# pwr_part.net
KiCad netlist of a schematic drawn in EAGLE
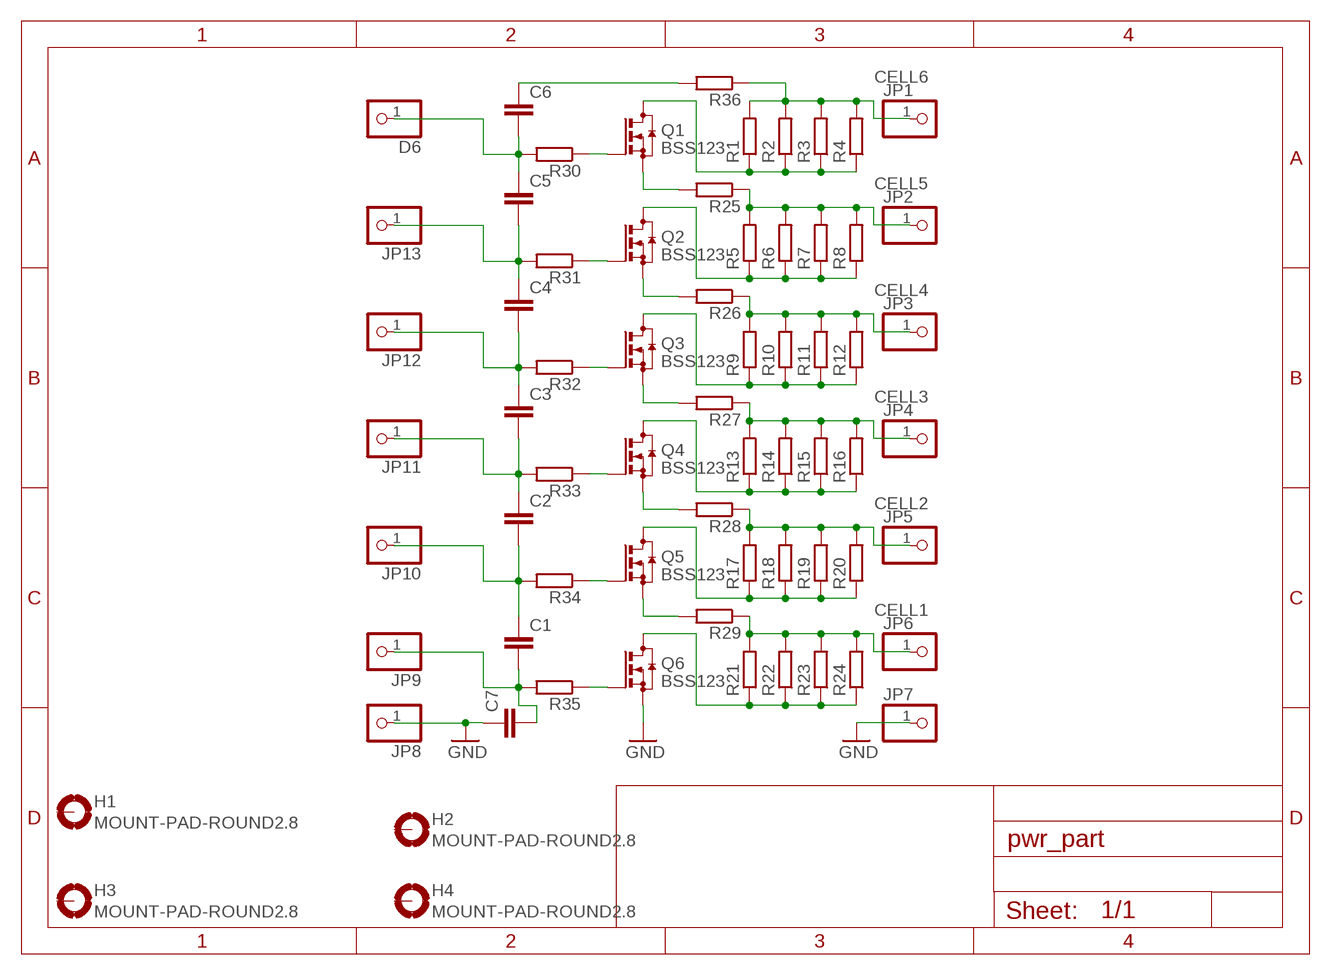
[diagram p0: schematic, sheet 1]

(export (version "E")
  (design (tool "Eeschema 10.0.6"))
  (components
    (comp (ref "C1")
      (value "C-EUC0805K")
      (footprint "eagle-import:C0805K")
      (libsource (lib "eagle-import") (part "C-EUC0805K"))
    )
    (comp (ref "C2")
      (value "C-EUC0805K")
      (footprint "eagle-import:C0805K")
      (libsource (lib "eagle-import") (part "C-EUC0805K"))
    )
    (comp (ref "C3")
      (value "C-EUC0805K")
      (footprint "eagle-import:C0805K")
      (libsource (lib "eagle-import") (part "C-EUC0805K"))
    )
    (comp (ref "C4")
      (value "C-EUC0805K")
      (footprint "eagle-import:C0805K")
      (libsource (lib "eagle-import") (part "C-EUC0805K"))
    )
    (comp (ref "C5")
      (value "C-EUC0805K")
      (footprint "eagle-import:C0805K")
      (libsource (lib "eagle-import") (part "C-EUC0805K"))
    )
    (comp (ref "C6")
      (value "C-EUC0805K")
      (footprint "eagle-import:C0805K")
      (libsource (lib "eagle-import") (part "C-EUC0805K"))
    )
    (comp (ref "C7")
      (value "C-EUC0805K")
      (footprint "eagle-import:C0805K")
      (libsource (lib "eagle-import") (part "C-EUC0805K"))
    )
    (comp (ref "D6")
      (value "PINHD-1X1")
      (footprint "eagle-import:1X01")
      (libsource (lib "eagle-import") (part "PINHD-1X1"))
    )
    (comp (ref "H1")
      (value "MOUNT-PAD-ROUND2.8")
      (footprint "eagle-import:2,8-PAD")
      (libsource (lib "eagle-import") (part "MOUNT-PAD-ROUND2.8"))
    )
    (comp (ref "H2")
      (value "MOUNT-PAD-ROUND2.8")
      (footprint "eagle-import:2,8-PAD")
      (libsource (lib "eagle-import") (part "MOUNT-PAD-ROUND2.8"))
    )
    (comp (ref "H3")
      (value "MOUNT-PAD-ROUND2.8")
      (footprint "eagle-import:2,8-PAD")
      (libsource (lib "eagle-import") (part "MOUNT-PAD-ROUND2.8"))
    )
    (comp (ref "H4")
      (value "MOUNT-PAD-ROUND2.8")
      (footprint "eagle-import:2,8-PAD")
      (libsource (lib "eagle-import") (part "MOUNT-PAD-ROUND2.8"))
    )
    (comp (ref "JP1")
      (value "PINHD-1X1")
      (footprint "eagle-import:1X01")
      (libsource (lib "eagle-import") (part "PINHD-1X1"))
    )
    (comp (ref "JP2")
      (value "PINHD-1X1")
      (footprint "eagle-import:1X01")
      (libsource (lib "eagle-import") (part "PINHD-1X1"))
    )
    (comp (ref "JP3")
      (value "PINHD-1X1")
      (footprint "eagle-import:1X01")
      (libsource (lib "eagle-import") (part "PINHD-1X1"))
    )
    (comp (ref "JP4")
      (value "PINHD-1X1")
      (footprint "eagle-import:1X01")
      (libsource (lib "eagle-import") (part "PINHD-1X1"))
    )
    (comp (ref "JP5")
      (value "PINHD-1X1")
      (footprint "eagle-import:1X01")
      (libsource (lib "eagle-import") (part "PINHD-1X1"))
    )
    (comp (ref "JP6")
      (value "PINHD-1X1")
      (footprint "eagle-import:1X01")
      (libsource (lib "eagle-import") (part "PINHD-1X1"))
    )
    (comp (ref "JP7")
      (value "PINHD-1X1")
      (footprint "eagle-import:1X01")
      (libsource (lib "eagle-import") (part "PINHD-1X1"))
    )
    (comp (ref "JP8")
      (value "PINHD-1X1")
      (footprint "eagle-import:1X01")
      (libsource (lib "eagle-import") (part "PINHD-1X1"))
    )
    (comp (ref "JP9")
      (value "PINHD-1X1")
      (footprint "eagle-import:1X01")
      (libsource (lib "eagle-import") (part "PINHD-1X1"))
    )
    (comp (ref "JP10")
      (value "PINHD-1X1")
      (footprint "eagle-import:1X01")
      (libsource (lib "eagle-import") (part "PINHD-1X1"))
    )
    (comp (ref "JP11")
      (value "PINHD-1X1")
      (footprint "eagle-import:1X01")
      (libsource (lib "eagle-import") (part "PINHD-1X1"))
    )
    (comp (ref "JP12")
      (value "PINHD-1X1")
      (footprint "eagle-import:1X01")
      (libsource (lib "eagle-import") (part "PINHD-1X1"))
    )
    (comp (ref "JP13")
      (value "PINHD-1X1")
      (footprint "eagle-import:1X01")
      (libsource (lib "eagle-import") (part "PINHD-1X1"))
    )
    (comp (ref "Q1")
      (value "BSS123")
      (footprint "eagle-import:SOT23")
      (libsource (lib "eagle-import") (part "BSS123"))
    )
    (comp (ref "Q2")
      (value "BSS123")
      (footprint "eagle-import:SOT23")
      (libsource (lib "eagle-import") (part "BSS123"))
    )
    (comp (ref "Q3")
      (value "BSS123")
      (footprint "eagle-import:SOT23")
      (libsource (lib "eagle-import") (part "BSS123"))
    )
    (comp (ref "Q4")
      (value "BSS123")
      (footprint "eagle-import:SOT23")
      (libsource (lib "eagle-import") (part "BSS123"))
    )
    (comp (ref "Q5")
      (value "BSS123")
      (footprint "eagle-import:SOT23")
      (libsource (lib "eagle-import") (part "BSS123"))
    )
    (comp (ref "Q6")
      (value "BSS123")
      (footprint "eagle-import:SOT23")
      (libsource (lib "eagle-import") (part "BSS123"))
    )
    (comp (ref "R1")
      (value "R-EU_R1206")
      (footprint "eagle-import:R1206")
      (libsource (lib "eagle-import") (part "R-EU_R1206"))
    )
    (comp (ref "R2")
      (value "R-EU_R1206")
      (footprint "eagle-import:R1206")
      (libsource (lib "eagle-import") (part "R-EU_R1206"))
    )
    (comp (ref "R3")
      (value "R-EU_R1206")
      (footprint "eagle-import:R1206")
      (libsource (lib "eagle-import") (part "R-EU_R1206"))
    )
    (comp (ref "R4")
      (value "R-EU_R1206")
      (footprint "eagle-import:R1206")
      (libsource (lib "eagle-import") (part "R-EU_R1206"))
    )
    (comp (ref "R5")
      (value "R-EU_R1206")
      (footprint "eagle-import:R1206")
      (libsource (lib "eagle-import") (part "R-EU_R1206"))
    )
    (comp (ref "R6")
      (value "R-EU_R1206")
      (footprint "eagle-import:R1206")
      (libsource (lib "eagle-import") (part "R-EU_R1206"))
    )
    (comp (ref "R7")
      (value "R-EU_R1206")
      (footprint "eagle-import:R1206")
      (libsource (lib "eagle-import") (part "R-EU_R1206"))
    )
    (comp (ref "R8")
      (value "R-EU_R1206")
      (footprint "eagle-import:R1206")
      (libsource (lib "eagle-import") (part "R-EU_R1206"))
    )
    (comp (ref "R9")
      (value "R-EU_R1206")
      (footprint "eagle-import:R1206")
      (libsource (lib "eagle-import") (part "R-EU_R1206"))
    )
    (comp (ref "R10")
      (value "R-EU_R1206")
      (footprint "eagle-import:R1206")
      (libsource (lib "eagle-import") (part "R-EU_R1206"))
    )
    (comp (ref "R11")
      (value "R-EU_R1206")
      (footprint "eagle-import:R1206")
      (libsource (lib "eagle-import") (part "R-EU_R1206"))
    )
    (comp (ref "R12")
      (value "R-EU_R1206")
      (footprint "eagle-import:R1206")
      (libsource (lib "eagle-import") (part "R-EU_R1206"))
    )
    (comp (ref "R13")
      (value "R-EU_R1206")
      (footprint "eagle-import:R1206")
      (libsource (lib "eagle-import") (part "R-EU_R1206"))
    )
    (comp (ref "R14")
      (value "R-EU_R1206")
      (footprint "eagle-import:R1206")
      (libsource (lib "eagle-import") (part "R-EU_R1206"))
    )
    (comp (ref "R15")
      (value "R-EU_R1206")
      (footprint "eagle-import:R1206")
      (libsource (lib "eagle-import") (part "R-EU_R1206"))
    )
    (comp (ref "R16")
      (value "R-EU_R1206")
      (footprint "eagle-import:R1206")
      (libsource (lib "eagle-import") (part "R-EU_R1206"))
    )
    (comp (ref "R17")
      (value "R-EU_R1206")
      (footprint "eagle-import:R1206")
      (libsource (lib "eagle-import") (part "R-EU_R1206"))
    )
    (comp (ref "R18")
      (value "R-EU_R1206")
      (footprint "eagle-import:R1206")
      (libsource (lib "eagle-import") (part "R-EU_R1206"))
    )
    (comp (ref "R19")
      (value "R-EU_R1206")
      (footprint "eagle-import:R1206")
      (libsource (lib "eagle-import") (part "R-EU_R1206"))
    )
    (comp (ref "R20")
      (value "R-EU_R1206")
      (footprint "eagle-import:R1206")
      (libsource (lib "eagle-import") (part "R-EU_R1206"))
    )
    (comp (ref "R21")
      (value "R-EU_R1206")
      (footprint "eagle-import:R1206")
      (libsource (lib "eagle-import") (part "R-EU_R1206"))
    )
    (comp (ref "R22")
      (value "R-EU_R1206")
      (footprint "eagle-import:R1206")
      (libsource (lib "eagle-import") (part "R-EU_R1206"))
    )
    (comp (ref "R23")
      (value "R-EU_R1206")
      (footprint "eagle-import:R1206")
      (libsource (lib "eagle-import") (part "R-EU_R1206"))
    )
    (comp (ref "R24")
      (value "R-EU_R1206")
      (footprint "eagle-import:R1206")
      (libsource (lib "eagle-import") (part "R-EU_R1206"))
    )
    (comp (ref "R25")
      (value "R-EU_0411/3V")
      (footprint "eagle-import:0411V")
      (libsource (lib "eagle-import") (part "R-EU_0411/3V"))
    )
    (comp (ref "R26")
      (value "R-EU_0411/3V")
      (footprint "eagle-import:0411V")
      (libsource (lib "eagle-import") (part "R-EU_0411/3V"))
    )
    (comp (ref "R27")
      (value "R-EU_0411/3V")
      (footprint "eagle-import:0411V")
      (libsource (lib "eagle-import") (part "R-EU_0411/3V"))
    )
    (comp (ref "R28")
      (value "R-EU_0411/3V")
      (footprint "eagle-import:0411V")
      (libsource (lib "eagle-import") (part "R-EU_0411/3V"))
    )
    (comp (ref "R29")
      (value "R-EU_0411/3V")
      (footprint "eagle-import:0411V")
      (libsource (lib "eagle-import") (part "R-EU_0411/3V"))
    )
    (comp (ref "R30")
      (value "R-EU_R1206")
      (footprint "eagle-import:R1206")
      (libsource (lib "eagle-import") (part "R-EU_R1206"))
    )
    (comp (ref "R31")
      (value "R-EU_R1206")
      (footprint "eagle-import:R1206")
      (libsource (lib "eagle-import") (part "R-EU_R1206"))
    )
    (comp (ref "R32")
      (value "R-EU_R1206")
      (footprint "eagle-import:R1206")
      (libsource (lib "eagle-import") (part "R-EU_R1206"))
    )
    (comp (ref "R33")
      (value "R-EU_R1206")
      (footprint "eagle-import:R1206")
      (libsource (lib "eagle-import") (part "R-EU_R1206"))
    )
    (comp (ref "R34")
      (value "R-EU_R1206")
      (footprint "eagle-import:R1206")
      (libsource (lib "eagle-import") (part "R-EU_R1206"))
    )
    (comp (ref "R35")
      (value "R-EU_R1206")
      (footprint "eagle-import:R1206")
      (libsource (lib "eagle-import") (part "R-EU_R1206"))
    )
    (comp (ref "R36")
      (value "R-EU_0411/3V")
      (footprint "eagle-import:0411V")
      (libsource (lib "eagle-import") (part "R-EU_0411/3V"))
    )
  )
  (nets
    (net (code "1") (name "/CELL1") (class "Default")
      (node (ref "JP6") (pin "1") (pinfunction "1_1") (pintype "passive"))
      (node (ref "R21") (pin "2") (pinfunction "2_2") (pintype "passive"))
      (node (ref "R22") (pin "2") (pinfunction "2_2") (pintype "passive"))
      (node (ref "R23") (pin "2") (pinfunction "2_2") (pintype "passive"))
      (node (ref "R24") (pin "2") (pinfunction "2_2") (pintype "passive"))
      (node (ref "R29") (pin "1") (pinfunction "1_1") (pintype "passive"))
    )
    (net (code "2") (name "/CELL2") (class "Default")
      (node (ref "JP5") (pin "1") (pinfunction "1_1") (pintype "passive"))
      (node (ref "R17") (pin "2") (pinfunction "2_2") (pintype "passive"))
      (node (ref "R18") (pin "2") (pinfunction "2_2") (pintype "passive"))
      (node (ref "R19") (pin "2") (pinfunction "2_2") (pintype "passive"))
      (node (ref "R20") (pin "2") (pinfunction "2_2") (pintype "passive"))
      (node (ref "R28") (pin "1") (pinfunction "1_1") (pintype "passive"))
    )
    (net (code "3") (name "/CELL3") (class "Default")
      (node (ref "JP4") (pin "1") (pinfunction "1_1") (pintype "passive"))
      (node (ref "R13") (pin "2") (pinfunction "2_2") (pintype "passive"))
      (node (ref "R14") (pin "2") (pinfunction "2_2") (pintype "passive"))
      (node (ref "R15") (pin "2") (pinfunction "2_2") (pintype "passive"))
      (node (ref "R16") (pin "2") (pinfunction "2_2") (pintype "passive"))
      (node (ref "R27") (pin "1") (pinfunction "1_1") (pintype "passive"))
    )
    (net (code "4") (name "/CELL4") (class "Default")
      (node (ref "JP3") (pin "1") (pinfunction "1_1") (pintype "passive"))
      (node (ref "R10") (pin "2") (pinfunction "2_2") (pintype "passive"))
      (node (ref "R11") (pin "2") (pinfunction "2_2") (pintype "passive"))
      (node (ref "R12") (pin "2") (pinfunction "2_2") (pintype "passive"))
      (node (ref "R26") (pin "1") (pinfunction "1_1") (pintype "passive"))
      (node (ref "R9") (pin "2") (pinfunction "2_2") (pintype "passive"))
    )
    (net (code "5") (name "/CELL5") (class "Default")
      (node (ref "JP2") (pin "1") (pinfunction "1_1") (pintype "passive"))
      (node (ref "R25") (pin "1") (pinfunction "1_1") (pintype "passive"))
      (node (ref "R5") (pin "2") (pinfunction "2_2") (pintype "passive"))
      (node (ref "R6") (pin "2") (pinfunction "2_2") (pintype "passive"))
      (node (ref "R7") (pin "2") (pinfunction "2_2") (pintype "passive"))
      (node (ref "R8") (pin "2") (pinfunction "2_2") (pintype "passive"))
    )
    (net (code "6") (name "/CELL6") (class "Default")
      (node (ref "JP1") (pin "1") (pinfunction "1_1") (pintype "passive"))
      (node (ref "R1") (pin "2") (pinfunction "2_2") (pintype "passive"))
      (node (ref "R2") (pin "2") (pinfunction "2_2") (pintype "passive"))
      (node (ref "R3") (pin "2") (pinfunction "2_2") (pintype "passive"))
      (node (ref "R36") (pin "1") (pinfunction "1_1") (pintype "passive"))
      (node (ref "R4") (pin "2") (pinfunction "2_2") (pintype "passive"))
    )
    (net (code "7") (name "GND") (class "Default")
      (node (ref "C7") (pin "1") (pinfunction "1_1") (pintype "passive"))
      (node (ref "JP7") (pin "1") (pinfunction "1_1") (pintype "passive"))
      (node (ref "JP8") (pin "1") (pinfunction "1_1") (pintype "passive"))
      (node (ref "Q6") (pin "2") (pinfunction "S_2") (pintype "passive"))
    )
    (net (code "8") (name "Net-(C1-Pad1)") (class "Default")
      (node (ref "C1") (pin "1") (pinfunction "1_1") (pintype "passive"))
      (node (ref "C2") (pin "2") (pinfunction "2_2") (pintype "passive"))
      (node (ref "JP10") (pin "1") (pinfunction "1_1") (pintype "passive"))
      (node (ref "R34") (pin "2") (pinfunction "2_2") (pintype "passive"))
    )
    (net (code "9") (name "Net-(C1-Pad2)") (class "Default")
      (node (ref "C1") (pin "2") (pinfunction "2_2") (pintype "passive"))
      (node (ref "C7") (pin "2") (pinfunction "2_2") (pintype "passive"))
      (node (ref "JP9") (pin "1") (pinfunction "1_1") (pintype "passive"))
      (node (ref "R35") (pin "2") (pinfunction "2_2") (pintype "passive"))
    )
    (net (code "10") (name "Net-(C2-Pad1)") (class "Default")
      (node (ref "C2") (pin "1") (pinfunction "1_1") (pintype "passive"))
      (node (ref "C3") (pin "2") (pinfunction "2_2") (pintype "passive"))
      (node (ref "JP11") (pin "1") (pinfunction "1_1") (pintype "passive"))
      (node (ref "R33") (pin "2") (pinfunction "2_2") (pintype "passive"))
    )
    (net (code "11") (name "Net-(C3-Pad1)") (class "Default")
      (node (ref "C3") (pin "1") (pinfunction "1_1") (pintype "passive"))
      (node (ref "C4") (pin "2") (pinfunction "2_2") (pintype "passive"))
      (node (ref "JP12") (pin "1") (pinfunction "1_1") (pintype "passive"))
      (node (ref "R32") (pin "2") (pinfunction "2_2") (pintype "passive"))
    )
    (net (code "12") (name "Net-(C4-Pad1)") (class "Default")
      (node (ref "C4") (pin "1") (pinfunction "1_1") (pintype "passive"))
      (node (ref "C5") (pin "2") (pinfunction "2_2") (pintype "passive"))
      (node (ref "JP13") (pin "1") (pinfunction "1_1") (pintype "passive"))
      (node (ref "R31") (pin "2") (pinfunction "2_2") (pintype "passive"))
    )
    (net (code "13") (name "Net-(C5-Pad1)") (class "Default")
      (node (ref "C5") (pin "1") (pinfunction "1_1") (pintype "passive"))
      (node (ref "C6") (pin "2") (pinfunction "2_2") (pintype "passive"))
      (node (ref "D6") (pin "1") (pinfunction "1_1") (pintype "passive"))
      (node (ref "R30") (pin "2") (pinfunction "2_2") (pintype "passive"))
    )
    (net (code "14") (name "Net-(C6-Pad1)") (class "Default")
      (node (ref "C6") (pin "1") (pinfunction "1_1") (pintype "passive"))
      (node (ref "R36") (pin "2") (pinfunction "2_2") (pintype "passive"))
    )
    (net (code "15") (name "Net-(Q1-D)") (class "Default")
      (node (ref "Q1") (pin "3") (pinfunction "D_3") (pintype "passive"))
      (node (ref "R1") (pin "1") (pinfunction "1_1") (pintype "passive"))
      (node (ref "R2") (pin "1") (pinfunction "1_1") (pintype "passive"))
      (node (ref "R3") (pin "1") (pinfunction "1_1") (pintype "passive"))
      (node (ref "R4") (pin "1") (pinfunction "1_1") (pintype "passive"))
    )
    (net (code "16") (name "Net-(Q1-G)") (class "Default")
      (node (ref "Q1") (pin "1") (pinfunction "G_1") (pintype "passive"))
      (node (ref "R30") (pin "1") (pinfunction "1_1") (pintype "passive"))
    )
    (net (code "17") (name "Net-(Q1-S)") (class "Default")
      (node (ref "Q1") (pin "2") (pinfunction "S_2") (pintype "passive"))
      (node (ref "R25") (pin "2") (pinfunction "2_2") (pintype "passive"))
    )
    (net (code "18") (name "Net-(Q2-D)") (class "Default")
      (node (ref "Q2") (pin "3") (pinfunction "D_3") (pintype "passive"))
      (node (ref "R5") (pin "1") (pinfunction "1_1") (pintype "passive"))
      (node (ref "R6") (pin "1") (pinfunction "1_1") (pintype "passive"))
      (node (ref "R7") (pin "1") (pinfunction "1_1") (pintype "passive"))
      (node (ref "R8") (pin "1") (pinfunction "1_1") (pintype "passive"))
    )
    (net (code "19") (name "Net-(Q2-G)") (class "Default")
      (node (ref "Q2") (pin "1") (pinfunction "G_1") (pintype "passive"))
      (node (ref "R31") (pin "1") (pinfunction "1_1") (pintype "passive"))
    )
    (net (code "20") (name "Net-(Q2-S)") (class "Default")
      (node (ref "Q2") (pin "2") (pinfunction "S_2") (pintype "passive"))
      (node (ref "R26") (pin "2") (pinfunction "2_2") (pintype "passive"))
    )
    (net (code "21") (name "Net-(Q3-D)") (class "Default")
      (node (ref "Q3") (pin "3") (pinfunction "D_3") (pintype "passive"))
      (node (ref "R10") (pin "1") (pinfunction "1_1") (pintype "passive"))
      (node (ref "R11") (pin "1") (pinfunction "1_1") (pintype "passive"))
      (node (ref "R12") (pin "1") (pinfunction "1_1") (pintype "passive"))
      (node (ref "R9") (pin "1") (pinfunction "1_1") (pintype "passive"))
    )
    (net (code "22") (name "Net-(Q3-G)") (class "Default")
      (node (ref "Q3") (pin "1") (pinfunction "G_1") (pintype "passive"))
      (node (ref "R32") (pin "1") (pinfunction "1_1") (pintype "passive"))
    )
    (net (code "23") (name "Net-(Q3-S)") (class "Default")
      (node (ref "Q3") (pin "2") (pinfunction "S_2") (pintype "passive"))
      (node (ref "R27") (pin "2") (pinfunction "2_2") (pintype "passive"))
    )
    (net (code "24") (name "Net-(Q4-D)") (class "Default")
      (node (ref "Q4") (pin "3") (pinfunction "D_3") (pintype "passive"))
      (node (ref "R13") (pin "1") (pinfunction "1_1") (pintype "passive"))
      (node (ref "R14") (pin "1") (pinfunction "1_1") (pintype "passive"))
      (node (ref "R15") (pin "1") (pinfunction "1_1") (pintype "passive"))
      (node (ref "R16") (pin "1") (pinfunction "1_1") (pintype "passive"))
    )
    (net (code "25") (name "Net-(Q4-G)") (class "Default")
      (node (ref "Q4") (pin "1") (pinfunction "G_1") (pintype "passive"))
      (node (ref "R33") (pin "1") (pinfunction "1_1") (pintype "passive"))
    )
    (net (code "26") (name "Net-(Q4-S)") (class "Default")
      (node (ref "Q4") (pin "2") (pinfunction "S_2") (pintype "passive"))
      (node (ref "R28") (pin "2") (pinfunction "2_2") (pintype "passive"))
    )
    (net (code "27") (name "Net-(Q5-D)") (class "Default")
      (node (ref "Q5") (pin "3") (pinfunction "D_3") (pintype "passive"))
      (node (ref "R17") (pin "1") (pinfunction "1_1") (pintype "passive"))
      (node (ref "R18") (pin "1") (pinfunction "1_1") (pintype "passive"))
      (node (ref "R19") (pin "1") (pinfunction "1_1") (pintype "passive"))
      (node (ref "R20") (pin "1") (pinfunction "1_1") (pintype "passive"))
    )
    (net (code "28") (name "Net-(Q5-G)") (class "Default")
      (node (ref "Q5") (pin "1") (pinfunction "G_1") (pintype "passive"))
      (node (ref "R34") (pin "1") (pinfunction "1_1") (pintype "passive"))
    )
    (net (code "29") (name "Net-(Q5-S)") (class "Default")
      (node (ref "Q5") (pin "2") (pinfunction "S_2") (pintype "passive"))
      (node (ref "R29") (pin "2") (pinfunction "2_2") (pintype "passive"))
    )
    (net (code "30") (name "Net-(Q6-D)") (class "Default")
      (node (ref "Q6") (pin "3") (pinfunction "D_3") (pintype "passive"))
      (node (ref "R21") (pin "1") (pinfunction "1_1") (pintype "passive"))
      (node (ref "R22") (pin "1") (pinfunction "1_1") (pintype "passive"))
      (node (ref "R23") (pin "1") (pinfunction "1_1") (pintype "passive"))
      (node (ref "R24") (pin "1") (pinfunction "1_1") (pintype "passive"))
    )
    (net (code "31") (name "Net-(Q6-G)") (class "Default")
      (node (ref "Q6") (pin "1") (pinfunction "G_1") (pintype "passive"))
      (node (ref "R35") (pin "1") (pinfunction "1_1") (pintype "passive"))
    )
    (net (code "32") (name "unconnected-(H1-MOUNT-PadB2,8)") (class "Default")
      (node (ref "H1") (pin "B2,8") (pinfunction "MOUNT_B2,8") (pintype "passive"))
    )
    (net (code "33") (name "unconnected-(H2-MOUNT-PadB2,8)") (class "Default")
      (node (ref "H2") (pin "B2,8") (pinfunction "MOUNT_B2,8") (pintype "passive"))
    )
    (net (code "34") (name "unconnected-(H3-MOUNT-PadB2,8)") (class "Default")
      (node (ref "H3") (pin "B2,8") (pinfunction "MOUNT_B2,8") (pintype "passive"))
    )
    (net (code "35") (name "unconnected-(H4-MOUNT-PadB2,8)") (class "Default")
      (node (ref "H4") (pin "B2,8") (pinfunction "MOUNT_B2,8") (pintype "passive"))
    )
  )
)
